# Connectors.net
KiCad netlist of a schematic drawn in Altium Designer
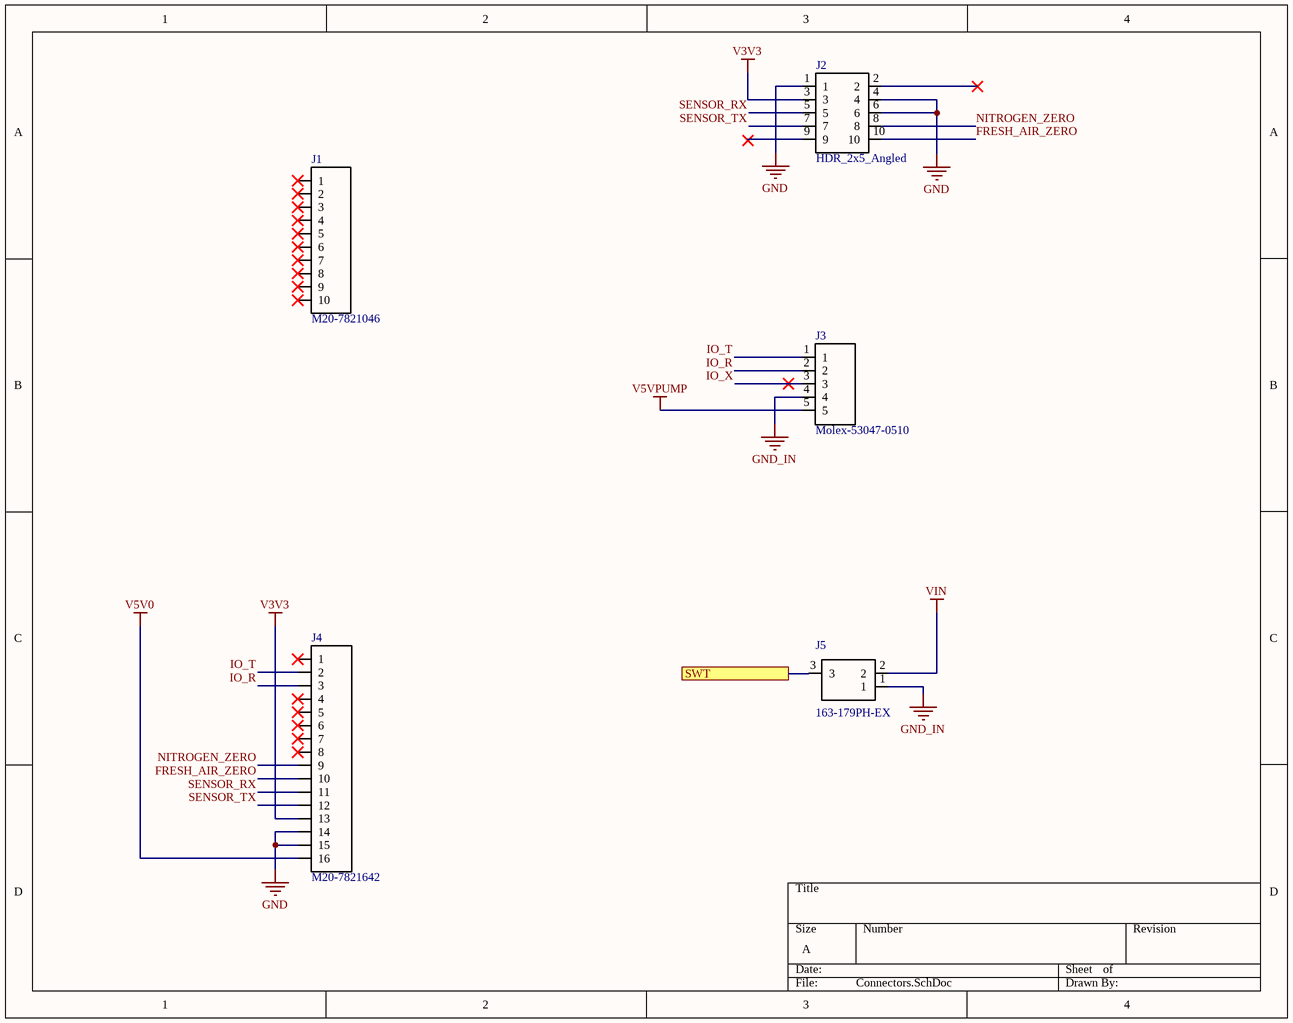
[diagram p0: Connectors.SchDoc]

(export (version "E")
  (design (tool "Eeschema 10.0.6"))
  (components
    (comp (ref "J1")
      (value "M20-7821046")
      (footprint "HDR1X10")
      (description "Connector")
      (fields (field (name "MOUSER2 PART NUMBER") "855-M20-7821046"))
      (libsource (lib "JMD_Parts") (part "M20-7821046"))
    )
    (comp (ref "J2")
      (value "HDR_2x5_Angled")
      (footprint "HDR2X5")
      (description "Connector")
      (fields
        (field (name "MOUSER2 PART NUMBER") "710-613010243121")
        (field (name "MANUFACTURER_PART_NUMBER") "613010243121")
      )
      (libsource (lib "JMD_Parts") (part "HDR_2x5_Angled"))
    )
    (comp (ref "J3")
      (value "Molex-53047-0510")
      (footprint "SHDR5W36P0X125_1X5_800X320X420P")
      (description "Connector")
      (fields
        (field (name "MOUSER2 PART NUMBER") "538-53047-0510")
        (field (name "MANUFACTURER_PART_NUMBER") "53047-0510")
      )
      (libsource (lib "JMD_Parts") (part "Molex-53047-0510"))
    )
    (comp (ref "J4")
      (value "M20-7821642")
      (footprint "HDR1X16")
      (description "Connector")
      (fields (field (name "MOUSER2 PART NUMBER") "855-M20-7821642"))
      (libsource (lib "JMD_Parts") (part "M20-7821642"))
    )
    (comp (ref "J5")
      (value "163-179PH-EX")
      (footprint "163179PHEX")
      (description "Connector")
      (libsource (lib "JMD_Parts") (part "163-179PH-EX"))
    )
  )
  (nets
    (net (code "1") (name "/FRESH_AIR_ZERO") (class "Default")
      (node (ref "J2") (pin "10") (pinfunction "10_10") (pintype "passive"))
      (node (ref "J4") (pin "10") (pinfunction "10_10") (pintype "passive"))
    )
    (net (code "2") (name "/IO_R") (class "Default")
      (node (ref "J3") (pin "2") (pinfunction "2_2") (pintype "passive"))
      (node (ref "J4") (pin "3") (pinfunction "3_3") (pintype "passive"))
    )
    (net (code "3") (name "/IO_T") (class "Default")
      (node (ref "J3") (pin "1") (pinfunction "1_1") (pintype "passive"))
      (node (ref "J4") (pin "2") (pinfunction "2_2") (pintype "passive"))
    )
    (net (code "4") (name "/IO_X") (class "Default")
      (node (ref "J3") (pin "3") (pinfunction "3_3") (pintype "passive"))
    )
    (net (code "5") (name "/NITROGEN_ZERO") (class "Default")
      (node (ref "J2") (pin "8") (pinfunction "8_8") (pintype "passive"))
      (node (ref "J4") (pin "9") (pinfunction "9_9") (pintype "passive"))
    )
    (net (code "6") (name "/SENSOR_RX") (class "Default")
      (node (ref "J2") (pin "5") (pinfunction "5_5") (pintype "passive"))
      (node (ref "J4") (pin "11") (pinfunction "11_11") (pintype "passive"))
    )
    (net (code "7") (name "/SENSOR_TX") (class "Default")
      (node (ref "J2") (pin "7") (pinfunction "7_7") (pintype "passive"))
      (node (ref "J4") (pin "12") (pinfunction "12_12") (pintype "passive"))
    )
    (net (code "8") (name "/SWT") (class "Default")
      (node (ref "J5") (pin "3") (pinfunction "3_3") (pintype "passive"))
    )
    (net (code "9") (name "GND") (class "Default")
      (node (ref "J2") (pin "1") (pinfunction "1_1") (pintype "passive"))
      (node (ref "J2") (pin "4") (pinfunction "4_4") (pintype "passive"))
      (node (ref "J2") (pin "6") (pinfunction "6_6") (pintype "passive"))
      (node (ref "J4") (pin "14") (pinfunction "14_14") (pintype "passive"))
      (node (ref "J4") (pin "15") (pinfunction "15_15") (pintype "passive"))
    )
    (net (code "10") (name "GND_IN") (class "Default")
      (node (ref "J3") (pin "4") (pinfunction "4_4") (pintype "passive"))
      (node (ref "J5") (pin "1") (pinfunction "1_1") (pintype "passive"))
    )
    (net (code "11") (name "V3V3") (class "Default")
      (node (ref "J2") (pin "3") (pinfunction "3_3") (pintype "passive"))
      (node (ref "J4") (pin "13") (pinfunction "13_13") (pintype "passive"))
    )
    (net (code "12") (name "V5V0") (class "Default")
      (node (ref "J4") (pin "16") (pinfunction "16_16") (pintype "passive"))
    )
    (net (code "13") (name "V5VPUMP") (class "Default")
      (node (ref "J3") (pin "5") (pinfunction "5_5") (pintype "passive"))
    )
    (net (code "14") (name "VIN") (class "Default")
      (node (ref "J5") (pin "2") (pinfunction "2_2") (pintype "passive"))
    )
    (net (code "15") (name "unconnected-(J1-Pad1)") (class "Default")
      (node (ref "J1") (pin "1") (pinfunction "1_1") (pintype "passive+no_connect"))
    )
    (net (code "16") (name "unconnected-(J1-Pad2)") (class "Default")
      (node (ref "J1") (pin "2") (pinfunction "2_2") (pintype "passive+no_connect"))
    )
    (net (code "17") (name "unconnected-(J1-Pad3)") (class "Default")
      (node (ref "J1") (pin "3") (pinfunction "3_3") (pintype "passive+no_connect"))
    )
    (net (code "18") (name "unconnected-(J1-Pad4)") (class "Default")
      (node (ref "J1") (pin "4") (pinfunction "4_4") (pintype "passive+no_connect"))
    )
    (net (code "19") (name "unconnected-(J1-Pad5)") (class "Default")
      (node (ref "J1") (pin "5") (pinfunction "5_5") (pintype "passive+no_connect"))
    )
    (net (code "20") (name "unconnected-(J1-Pad6)") (class "Default")
      (node (ref "J1") (pin "6") (pinfunction "6_6") (pintype "passive+no_connect"))
    )
    (net (code "21") (name "unconnected-(J1-Pad7)") (class "Default")
      (node (ref "J1") (pin "7") (pinfunction "7_7") (pintype "passive+no_connect"))
    )
    (net (code "22") (name "unconnected-(J1-Pad8)") (class "Default")
      (node (ref "J1") (pin "8") (pinfunction "8_8") (pintype "passive+no_connect"))
    )
    (net (code "23") (name "unconnected-(J1-Pad9)") (class "Default")
      (node (ref "J1") (pin "9") (pinfunction "9_9") (pintype "passive+no_connect"))
    )
    (net (code "24") (name "unconnected-(J1-Pad10)") (class "Default")
      (node (ref "J1") (pin "10") (pinfunction "10_10") (pintype "passive+no_connect"))
    )
    (net (code "25") (name "unconnected-(J2-Pad2)") (class "Default")
      (node (ref "J2") (pin "2") (pinfunction "2_2") (pintype "passive+no_connect"))
    )
    (net (code "26") (name "unconnected-(J2-Pad9)") (class "Default")
      (node (ref "J2") (pin "9") (pinfunction "9_9") (pintype "passive+no_connect"))
    )
    (net (code "27") (name "unconnected-(J4-Pad1)") (class "Default")
      (node (ref "J4") (pin "1") (pinfunction "1_1") (pintype "passive+no_connect"))
    )
    (net (code "28") (name "unconnected-(J4-Pad4)") (class "Default")
      (node (ref "J4") (pin "4") (pinfunction "4_4") (pintype "passive+no_connect"))
    )
    (net (code "29") (name "unconnected-(J4-Pad5)") (class "Default")
      (node (ref "J4") (pin "5") (pinfunction "5_5") (pintype "passive+no_connect"))
    )
    (net (code "30") (name "unconnected-(J4-Pad6)") (class "Default")
      (node (ref "J4") (pin "6") (pinfunction "6_6") (pintype "passive+no_connect"))
    )
    (net (code "31") (name "unconnected-(J4-Pad7)") (class "Default")
      (node (ref "J4") (pin "7") (pinfunction "7_7") (pintype "passive+no_connect"))
    )
    (net (code "32") (name "unconnected-(J4-Pad8)") (class "Default")
      (node (ref "J4") (pin "8") (pinfunction "8_8") (pintype "passive+no_connect"))
    )
  )
)
